# MCU089A_AltRouting_Misc.net
KiCad netlist of a schematic drawn in Altium Designer
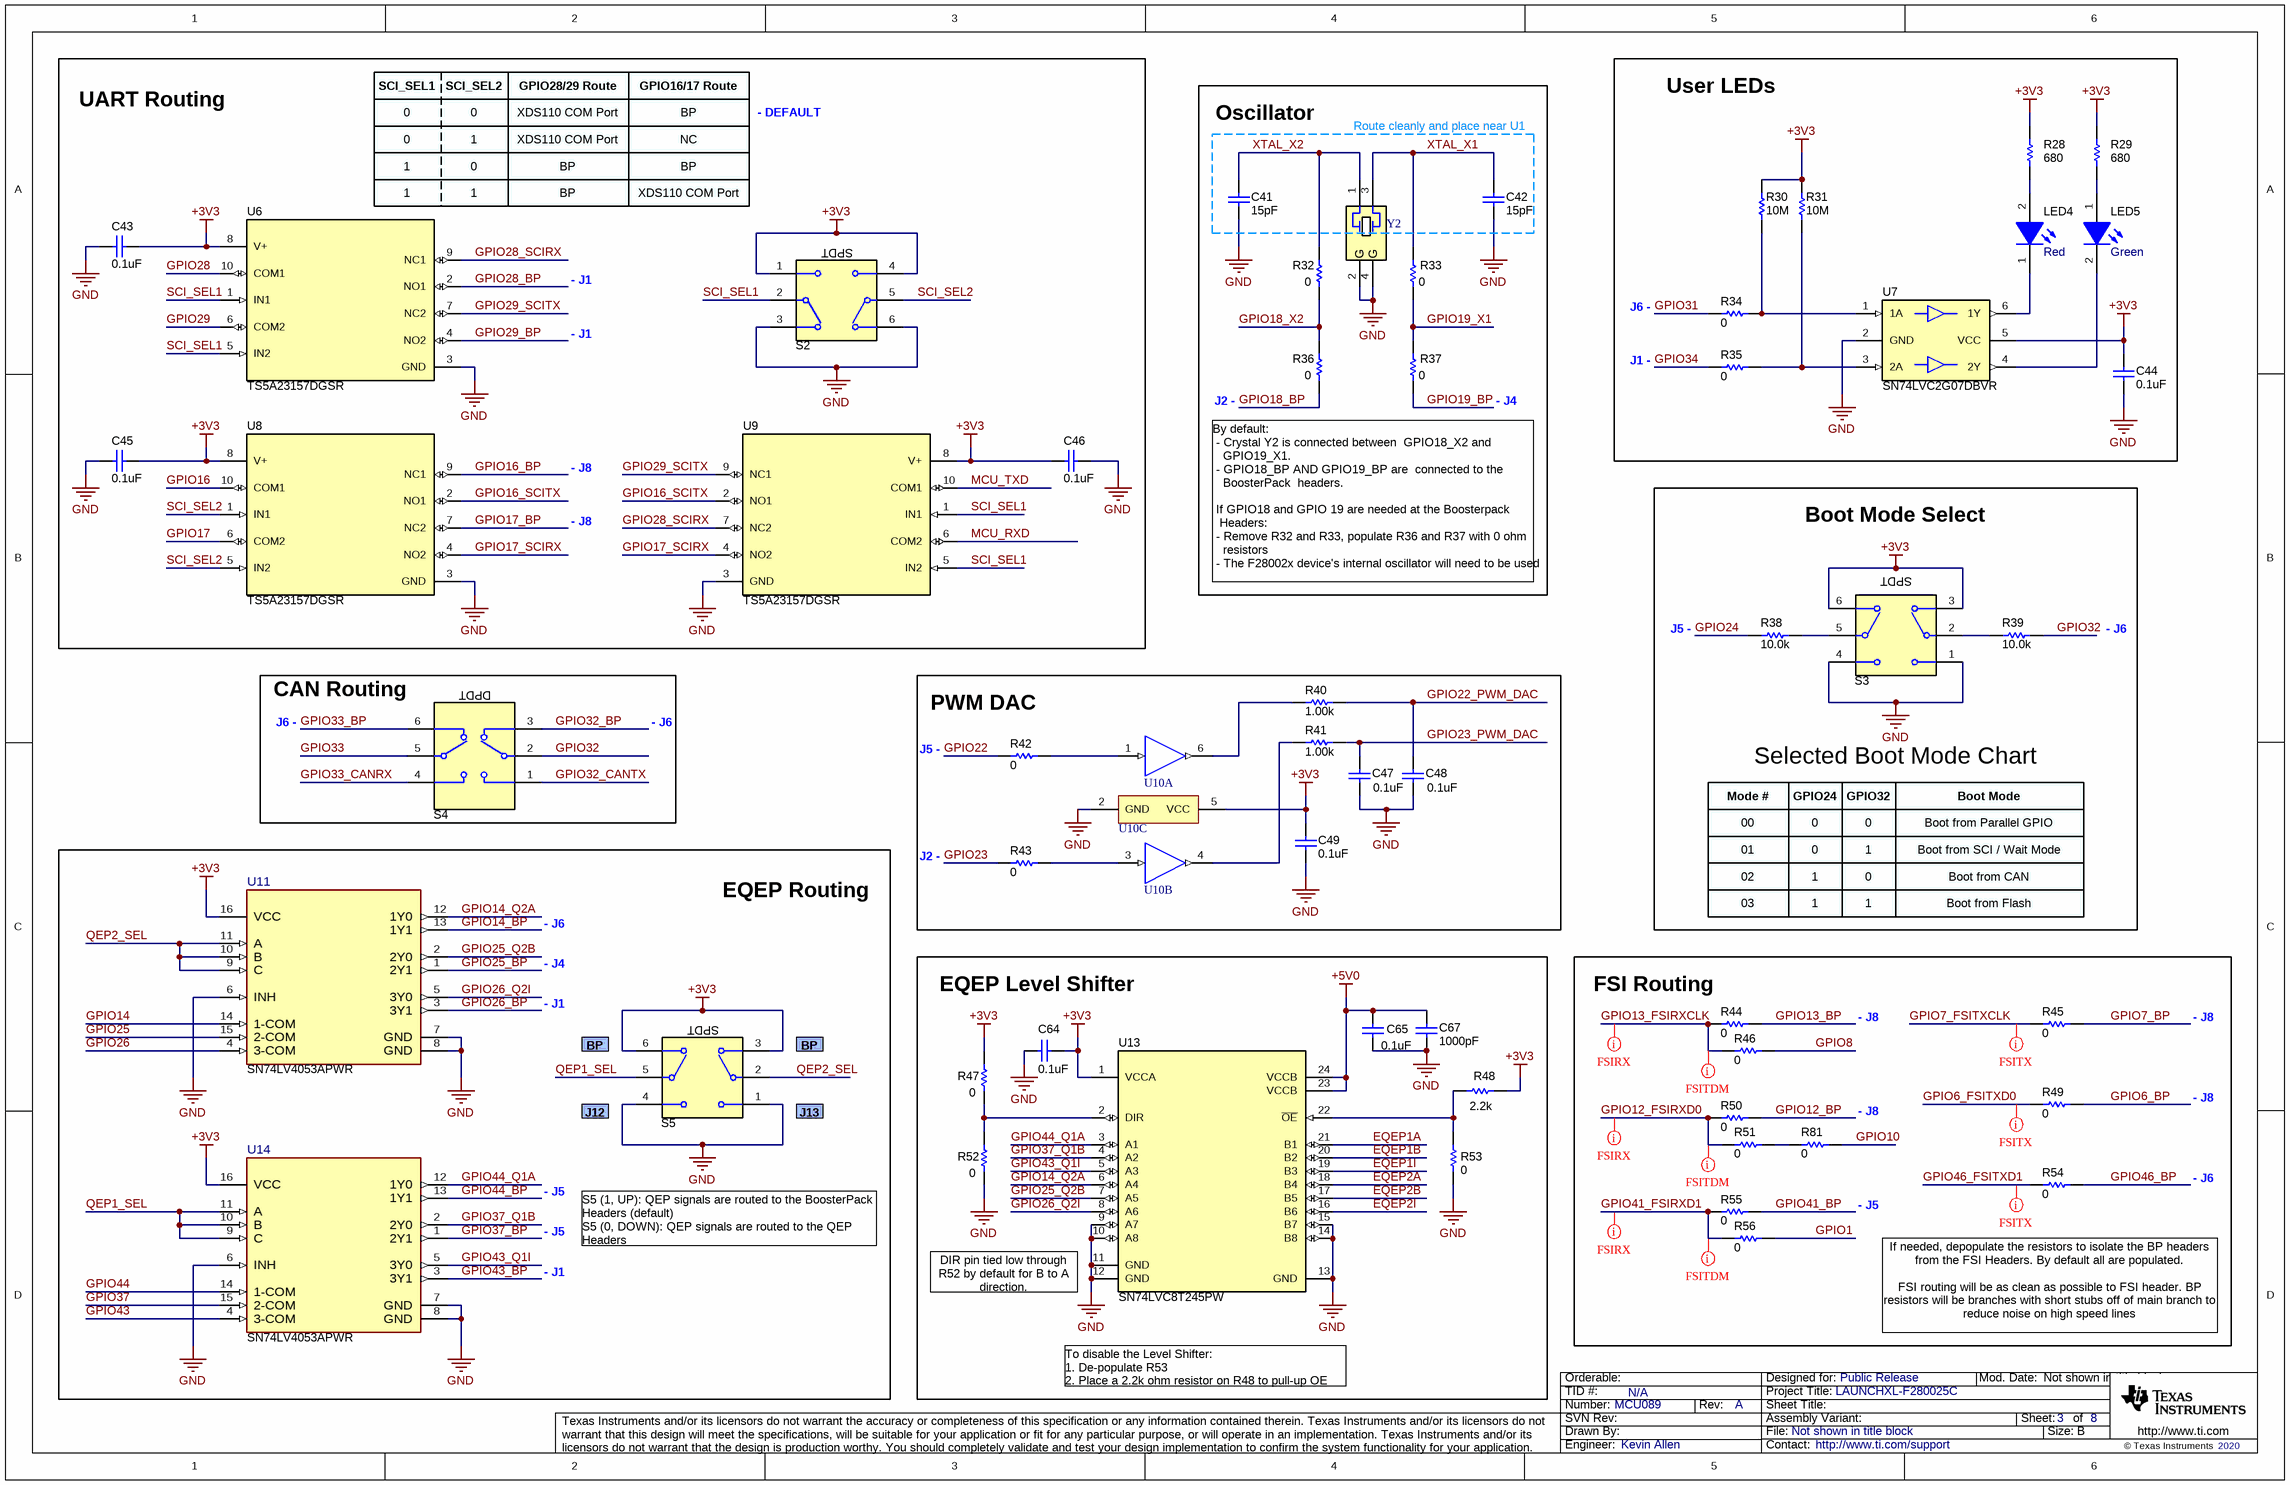
[diagram p0: MCU089A_AltRouting_Misc.SchDoc]

(export (version "E")
  (design (tool "Eeschema 10.0.6"))
  (components
    (comp (ref "C41")
      (value "885012005056")
      (footprint "0402")
      (description "CAP, CERM, 15 pF, 50 V, +/- 5%, C0G/NP0, 0402")
      (fields
        (field (name "VALUEDISPLAYED") "15pF")
        (field (name "MANUFACTURER") "Wurth Elektronik")
        (field (name "PUBLISHER") "Texas Instruments")
      )
      (libsource (lib "Altium Vault - TI") (part "Capacitor"))
    )
    (comp (ref "C42")
      (value "885012005056")
      (footprint "0402")
      (description "CAP, CERM, 15 pF, 50 V, +/- 5%, C0G/NP0, 0402")
      (fields
        (field (name "VALUEDISPLAYED") "15pF")
        (field (name "MANUFACTURER") "Wurth Elektronik")
        (field (name "PUBLISHER") "Texas Instruments")
      )
      (libsource (lib "Altium Vault - TI") (part "Capacitor"))
    )
    (comp (ref "C43")
      (value "GRM155R71A104KA01D")
      (footprint "0402")
      (description "CAP, CERM, 0.1 uF, 10 V, +/- 10%, X7R, 0402")
      (fields
        (field (name "VALUEDISPLAYED") "0.1uF")
        (field (name "MANUFACTURER") "MuRata")
        (field (name "PUBLISHER") "Texas Instruments")
      )
      (libsource (lib "Altium Vault - TI") (part "Capacitor"))
    )
    (comp (ref "C44")
      (value "GRM155R71A104KA01D")
      (footprint "0402")
      (description "CAP, CERM, 0.1 uF, 10 V, +/- 10%, X7R, 0402")
      (fields
        (field (name "VALUEDISPLAYED") "0.1uF")
        (field (name "MANUFACTURER") "MuRata")
        (field (name "PUBLISHER") "Texas Instruments")
      )
      (libsource (lib "Altium Vault - TI") (part "Capacitor"))
    )
    (comp (ref "C45")
      (value "GRM155R71A104KA01D")
      (footprint "0402")
      (description "CAP, CERM, 0.1 uF, 10 V, +/- 10%, X7R, 0402")
      (fields
        (field (name "VALUEDISPLAYED") "0.1uF")
        (field (name "MANUFACTURER") "MuRata")
        (field (name "PUBLISHER") "Texas Instruments")
      )
      (libsource (lib "Altium Vault - TI") (part "Capacitor"))
    )
    (comp (ref "C46")
      (value "GRM155R71A104KA01D")
      (footprint "0402")
      (description "CAP, CERM, 0.1 uF, 10 V, +/- 10%, X7R, 0402")
      (fields
        (field (name "VALUEDISPLAYED") "0.1uF")
        (field (name "MANUFACTURER") "MuRata")
        (field (name "PUBLISHER") "Texas Instruments")
      )
      (libsource (lib "Altium Vault - TI") (part "Capacitor"))
    )
    (comp (ref "C47")
      (value "TMK105B7104MV-FR")
      (footprint "0402")
      (description "CAP, CERM, 0.1 uF, 25 V, +/- 20%, X7R, 0402")
      (fields
        (field (name "MANUFACTURER") "Taiyo Yuden")
        (field (name "VALUEDISPLAYED") "0.1uF")
        (field (name "PUBLISHER") "Texas Instruments")
      )
      (libsource (lib "Altium Vault - TI") (part "Capacitor"))
    )
    (comp (ref "C48")
      (value "TMK105B7104MV-FR")
      (footprint "0402")
      (description "CAP, CERM, 0.1 uF, 25 V, +/- 20%, X7R, 0402")
      (fields
        (field (name "MANUFACTURER") "Taiyo Yuden")
        (field (name "VALUEDISPLAYED") "0.1uF")
        (field (name "PUBLISHER") "Texas Instruments")
      )
      (libsource (lib "Altium Vault - TI") (part "Capacitor"))
    )
    (comp (ref "C49")
      (value "GRM155R71A104KA01D")
      (footprint "0402")
      (description "CAP, CERM, 0.1 uF, 10 V, +/- 10%, X7R, 0402")
      (fields
        (field (name "VALUEDISPLAYED") "0.1uF")
        (field (name "MANUFACTURER") "MuRata")
        (field (name "PUBLISHER") "Texas Instruments")
      )
      (libsource (lib "Altium Vault - TI") (part "Capacitor"))
    )
    (comp (ref "C64")
      (value "GRM155R71A104KA01D")
      (footprint "0402")
      (description "CAP, CERM, 0.1 uF, 10 V, +/- 10%, X7R, 0402")
      (fields
        (field (name "VALUEDISPLAYED") "0.1uF")
        (field (name "MANUFACTURER") "MuRata")
        (field (name "PUBLISHER") "Texas Instruments")
      )
      (libsource (lib "Altium Vault - TI") (part "Capacitor"))
    )
    (comp (ref "C65")
      (value "GRM155R71A104KA01D")
      (footprint "0402")
      (description "CAP, CERM, 0.1 uF, 10 V, +/- 10%, X7R, 0402")
      (fields
        (field (name "VALUEDISPLAYED") "0.1uF")
        (field (name "MANUFACTURER") "MuRata")
        (field (name "PUBLISHER") "Texas Instruments")
      )
      (libsource (lib "Altium Vault - TI") (part "Capacitor"))
    )
    (comp (ref "C67")
      (value "885012205061")
      (footprint "0402")
      (description "CAP, CERM, 1000 pF, 50 V, +/- 10%, X7R, 0402")
      (fields
        (field (name "VALUEDISPLAYED") "1000pF")
        (field (name "MANUFACTURER") "Wurth Elektronik")
        (field (name "PUBLISHER") "Texas Instruments")
      )
      (libsource (lib "Altium Vault - TI") (part "Capacitor"))
    )
    (comp (ref "LED4")
      (value "Red")
      (footprint "WL-SMCW_RED_0805")
      (description "LED, Red, SMD")
      (fields (field (name "MANUFACTURER") "Wurth Elektronik") (field (name "PARTNUMBER") "150080SS75000"))
      (libsource (lib "Altium Vault - TI") (part "LED_A2_K1"))
    )
    (comp (ref "LED5")
      (value "Green")
      (footprint "LED_LTST-C171")
      (description "LED, Green, SMD")
      (fields (field (name "MANUFACTURER") "Lite-On") (field (name "PARTNUMBER") "LTST-C171GKT"))
      (libsource (lib "Altium Vault - TI") (part "LED"))
    )
    (comp (ref "R28")
      (value "CRCW0402680RJNED")
      (footprint "0402")
      (description "RES, 680, 5%, 0.063 W, AEC-Q200 Grade 0, 0402")
      (fields (field (name "MANUFACTURER") "Vishay-Dale") (field (name "VALUEDISPLAYED") "680"))
      (libsource (lib "Altium Vault - TI") (part "CMP-0026962-3"))
    )
    (comp (ref "R29")
      (value "CRCW0402680RJNED")
      (footprint "0402")
      (description "RES, 680, 5%, 0.063 W, AEC-Q200 Grade 0, 0402")
      (fields (field (name "MANUFACTURER") "Vishay-Dale") (field (name "VALUEDISPLAYED") "680"))
      (libsource (lib "Altium Vault - TI") (part "CMP-0026962-3"))
    )
    (comp (ref "R30")
      (value "CRCW040210M0JNED")
      (footprint "0402")
      (description "RES, 10 M, 5%, 0.063 W, AEC-Q200 Grade 0, 0402")
      (fields (field (name "VALUEDISPLAYED") "10M") (field (name "MANUFACTURER") "Vishay-Dale"))
      (libsource (lib "Altium Vault - TI") (part "Resistor"))
    )
    (comp (ref "R31")
      (value "CRCW040210M0JNED")
      (footprint "0402")
      (description "RES, 10 M, 5%, 0.063 W, AEC-Q200 Grade 0, 0402")
      (fields (field (name "VALUEDISPLAYED") "10M") (field (name "MANUFACTURER") "Vishay-Dale"))
      (libsource (lib "Altium Vault - TI") (part "Resistor"))
    )
    (comp (ref "R32")
      (value "CRCW06030000Z0EA")
      (footprint "0603")
      (description "RES, 0, 5%, 0.1 W, AEC-Q200 Grade 0, 0603")
      (fields (field (name "VALUEDISPLAYED") "0") (field (name "MANUFACTURER") "Vishay-Dale"))
      (libsource (lib "Altium Vault - TI") (part "Resistor"))
    )
    (comp (ref "R33")
      (value "CRCW06030000Z0EA")
      (footprint "0603")
      (description "RES, 0, 5%, 0.1 W, AEC-Q200 Grade 0, 0603")
      (fields (field (name "VALUEDISPLAYED") "0") (field (name "MANUFACTURER") "Vishay-Dale"))
      (libsource (lib "Altium Vault - TI") (part "Resistor"))
    )
    (comp (ref "R34")
      (value "CRCW06030000Z0EA")
      (footprint "0603")
      (description "RES, 0, 5%, 0.1 W, AEC-Q200 Grade 0, 0603")
      (fields (field (name "VALUEDISPLAYED") "0") (field (name "MANUFACTURER") "Vishay-Dale"))
      (libsource (lib "Altium Vault - TI") (part "Resistor"))
    )
    (comp (ref "R35")
      (value "CRCW06030000Z0EA")
      (footprint "0603")
      (description "RES, 0, 5%, 0.1 W, AEC-Q200 Grade 0, 0603")
      (fields (field (name "VALUEDISPLAYED") "0") (field (name "MANUFACTURER") "Vishay-Dale"))
      (libsource (lib "Altium Vault - TI") (part "Resistor"))
    )
    (comp (ref "R36")
      (value "CRCW06030000Z0EA")
      (footprint "0603")
      (description "RES, 0, 5%, 0.1 W, AEC-Q200 Grade 0, 0603")
      (fields (field (name "VALUEDISPLAYED") "0") (field (name "MANUFACTURER") "Vishay-Dale"))
      (libsource (lib "Altium Vault - TI") (part "Resistor"))
    )
    (comp (ref "R37")
      (value "CRCW06030000Z0EA")
      (footprint "0603")
      (description "RES, 0, 5%, 0.1 W, AEC-Q200 Grade 0, 0603")
      (fields (field (name "VALUEDISPLAYED") "0") (field (name "MANUFACTURER") "Vishay-Dale"))
      (libsource (lib "Altium Vault - TI") (part "Resistor"))
    )
    (comp (ref "R38")
      (value "RC0603FR-0710KL")
      (footprint "0603")
      (description "RES, 10.0 k, 1%, 0.1 W, 0603")
      (fields (field (name "MANUFACTURER") "Yageo") (field (name "VALUEDISPLAYED") "10.0k"))
      (libsource (lib "Altium Vault - TI") (part "Resistor"))
    )
    (comp (ref "R39")
      (value "RC0603FR-0710KL")
      (footprint "0603")
      (description "RES, 10.0 k, 1%, 0.1 W, 0603")
      (fields (field (name "MANUFACTURER") "Yageo") (field (name "VALUEDISPLAYED") "10.0k"))
      (libsource (lib "Altium Vault - TI") (part "Resistor"))
    )
    (comp (ref "R40")
      (value "CRCW04021K00FKED")
      (footprint "0402")
      (description "RES, 1.00 k, 1%, 0.063 W, AEC-Q200 Grade 0, 0402")
      (fields (field (name "MANUFACTURER") "Vishay-Dale") (field (name "VALUEDISPLAYED") "1.00k"))
      (libsource (lib "Altium Vault - TI") (part "Resistor"))
    )
    (comp (ref "R41")
      (value "CRCW04021K00FKED")
      (footprint "0402")
      (description "RES, 1.00 k, 1%, 0.063 W, AEC-Q200 Grade 0, 0402")
      (fields (field (name "MANUFACTURER") "Vishay-Dale") (field (name "VALUEDISPLAYED") "1.00k"))
      (libsource (lib "Altium Vault - TI") (part "Resistor"))
    )
    (comp (ref "R42")
      (value "CRCW06030000Z0EA")
      (footprint "0603")
      (description "RES, 0, 5%, 0.1 W, AEC-Q200 Grade 0, 0603")
      (fields (field (name "VALUEDISPLAYED") "0") (field (name "MANUFACTURER") "Vishay-Dale"))
      (libsource (lib "Altium Vault - TI") (part "Resistor"))
    )
    (comp (ref "R43")
      (value "CRCW06030000Z0EA")
      (footprint "0603")
      (description "RES, 0, 5%, 0.1 W, AEC-Q200 Grade 0, 0603")
      (fields (field (name "VALUEDISPLAYED") "0") (field (name "MANUFACTURER") "Vishay-Dale"))
      (libsource (lib "Altium Vault - TI") (part "Resistor"))
    )
    (comp (ref "R44")
      (value "CRCW06030000Z0EA")
      (footprint "0603")
      (description "RES, 0, 5%, 0.1 W, AEC-Q200 Grade 0, 0603")
      (fields (field (name "VALUEDISPLAYED") "0") (field (name "MANUFACTURER") "Vishay-Dale"))
      (libsource (lib "Altium Vault - TI") (part "Resistor"))
    )
    (comp (ref "R45")
      (value "CRCW06030000Z0EA")
      (footprint "0603")
      (description "RES, 0, 5%, 0.1 W, AEC-Q200 Grade 0, 0603")
      (fields (field (name "VALUEDISPLAYED") "0") (field (name "MANUFACTURER") "Vishay-Dale"))
      (libsource (lib "Altium Vault - TI") (part "Resistor"))
    )
    (comp (ref "R46")
      (value "CRCW06030000Z0EA")
      (footprint "0603")
      (description "RES, 0, 5%, 0.1 W, AEC-Q200 Grade 0, 0603")
      (fields (field (name "VALUEDISPLAYED") "0") (field (name "MANUFACTURER") "Vishay-Dale"))
      (libsource (lib "Altium Vault - TI") (part "Resistor"))
    )
    (comp (ref "R47")
      (value "CRCW06030000Z0EA")
      (footprint "0603")
      (description "RES, 0, 5%, 0.1 W, AEC-Q200 Grade 0, 0603")
      (fields (field (name "VALUEDISPLAYED") "0") (field (name "MANUFACTURER") "Vishay-Dale"))
      (libsource (lib "Altium Vault - TI") (part "Resistor"))
    )
    (comp (ref "R48")
      (value "CRCW06032K20JNEA")
      (footprint "0603")
      (description "RES, 2.2 k, 5%, 0.1 W, AEC-Q200 Grade 0, 0603")
      (fields (field (name "VALUEDISPLAYED") "2.2k") (field (name "MANUFACTURER") "Vishay-Dale"))
      (libsource (lib "Altium Vault - TI") (part "Resistor"))
    )
    (comp (ref "R49")
      (value "CRCW06030000Z0EA")
      (footprint "0603")
      (description "RES, 0, 5%, 0.1 W, AEC-Q200 Grade 0, 0603")
      (fields (field (name "VALUEDISPLAYED") "0") (field (name "MANUFACTURER") "Vishay-Dale"))
      (libsource (lib "Altium Vault - TI") (part "Resistor"))
    )
    (comp (ref "R50")
      (value "CRCW06030000Z0EA")
      (footprint "0603")
      (description "RES, 0, 5%, 0.1 W, AEC-Q200 Grade 0, 0603")
      (fields (field (name "VALUEDISPLAYED") "0") (field (name "MANUFACTURER") "Vishay-Dale"))
      (libsource (lib "Altium Vault - TI") (part "Resistor"))
    )
    (comp (ref "R51")
      (value "CRCW06030000Z0EA")
      (footprint "0603")
      (description "RES, 0, 5%, 0.1 W, AEC-Q200 Grade 0, 0603")
      (fields (field (name "VALUEDISPLAYED") "0") (field (name "MANUFACTURER") "Vishay-Dale"))
      (libsource (lib "Altium Vault - TI") (part "Resistor"))
    )
    (comp (ref "R52")
      (value "CRCW06030000Z0EA")
      (footprint "0603")
      (description "RES, 0, 5%, 0.1 W, AEC-Q200 Grade 0, 0603")
      (fields (field (name "VALUEDISPLAYED") "0") (field (name "MANUFACTURER") "Vishay-Dale"))
      (libsource (lib "Altium Vault - TI") (part "Resistor"))
    )
    (comp (ref "R53")
      (value "CRCW06030000Z0EA")
      (footprint "0603")
      (description "RES, 0, 5%, 0.1 W, AEC-Q200 Grade 0, 0603")
      (fields (field (name "VALUEDISPLAYED") "0") (field (name "MANUFACTURER") "Vishay-Dale"))
      (libsource (lib "Altium Vault - TI") (part "Resistor"))
    )
    (comp (ref "R54")
      (value "CRCW06030000Z0EA")
      (footprint "0603")
      (description "RES, 0, 5%, 0.1 W, AEC-Q200 Grade 0, 0603")
      (fields (field (name "VALUEDISPLAYED") "0") (field (name "MANUFACTURER") "Vishay-Dale"))
      (libsource (lib "Altium Vault - TI") (part "Resistor"))
    )
    (comp (ref "R55")
      (value "CRCW06030000Z0EA")
      (footprint "0603")
      (description "RES, 0, 5%, 0.1 W, AEC-Q200 Grade 0, 0603")
      (fields (field (name "VALUEDISPLAYED") "0") (field (name "MANUFACTURER") "Vishay-Dale"))
      (libsource (lib "Altium Vault - TI") (part "Resistor"))
    )
    (comp (ref "R56")
      (value "CRCW06030000Z0EA")
      (footprint "0603")
      (description "RES, 0, 5%, 0.1 W, AEC-Q200 Grade 0, 0603")
      (fields (field (name "VALUEDISPLAYED") "0") (field (name "MANUFACTURER") "Vishay-Dale"))
      (libsource (lib "Altium Vault - TI") (part "Resistor"))
    )
    (comp (ref "R81")
      (value "CRCW06030000Z0EA")
      (footprint "0603")
      (description "RES, 0, 5%, 0.1 W, AEC-Q200 Grade 0, 0603")
      (fields (field (name "VALUEDISPLAYED") "0") (field (name "MANUFACTURER") "Vishay-Dale"))
      (libsource (lib "Altium Vault - TI") (part "Resistor"))
    )
    (comp (ref "S2")
      (value "CAS-D20TA")
      (footprint "SW_CAS-D20TA")
      (description "Switch, Dual SPDT,  2 Pos, 0.1A, 6VDC, SMD")
      (fields
        (field (name "MANUFACTURER") "Copal Electronics")
        (field (name "PUBLISHER") "Texas Instruments")
      )
      (libsource (lib "") (part "SW_SPDT_CAS-D20TA_1"))
    )
    (comp (ref "S3")
      (value "CAS-D20TA")
      (footprint "SW_CAS-D20TA")
      (description "Switch, Dual SPDT,  2 Pos, 0.1A, 6VDC, SMD")
      (fields
        (field (name "MANUFACTURER") "Copal Electronics")
        (field (name "PUBLISHER") "Texas Instruments")
      )
      (libsource (lib "Altium Vault - TI") (part "SW_SPDT_CAS-D20TA"))
    )
    (comp (ref "S4")
      (value "CAS-220TA")
      (footprint "SW_CAS-220TA")
      (description "SLIDE SWITCH DPDT  .1A, SMT")
      (fields
        (field (name "MANUFACTURER") "Copal Electronics")
        (field (name "PUBLISHER") "Texas Instruments")
      )
      (libsource (lib "Altium Vault - TI") (part "SW_CAS-220TA"))
    )
    (comp (ref "S5")
      (value "CAS-D20TA")
      (footprint "SW_CAS-D20TA")
      (description "Switch, Dual SPDT,  2 Pos, 0.1A, 6VDC, SMD")
      (fields
        (field (name "MANUFACTURER") "Copal Electronics")
        (field (name "PUBLISHER") "Texas Instruments")
      )
      (libsource (lib "Altium Vault - TI") (part "SW_SPDT_CAS-D20TA"))
    )
    (comp (ref "U6")
      (value "TS5A23157DGSR")
      (footprint "DGS0010A_N")
      (description "DUAL 10-Ohm SPDT ANALOG SWITCH, DGS0010A (VSSOP-10)")
      (fields
        (field (name "ALTERNATE PARTNUMBER") "TS5A23157DGST")
        (field (name "MANUFACTURER") "Texas Instruments")
        (field (name "PARTNUMBER") "TS5A23157DGSR")
        (field (name "PUBLISHER") "Texas Instruments")
      )
      (libsource (lib "Altium Vault - TI") (part "TS5A23159"))
    )
    (comp (ref "U7")
      (value "SN74LVC2G07DBVR")
      (footprint "DBV0006A_N")
      (description "Dual Buffer/Driver with Open-Drain Output, DBV0006A, LARGE T&R")
      (fields
        (field (name "GENERIC PART NUMBER") "SN74LVC2G07")
        (field (name "MANUFACTURER") "Texas Instruments")
      )
      (libsource (lib "Altium Vault - TI") (part "CMP-0051789-2"))
    )
    (comp (ref "U8")
      (value "TS5A23157DGSR")
      (footprint "DGS0010A_N")
      (description "DUAL 10-Ohm SPDT ANALOG SWITCH, DGS0010A (VSSOP-10)")
      (fields
        (field (name "ALTERNATE PARTNUMBER") "TS5A23157DGST")
        (field (name "MANUFACTURER") "Texas Instruments")
        (field (name "PARTNUMBER") "TS5A23157DGSR")
        (field (name "PUBLISHER") "Texas Instruments")
      )
      (libsource (lib "Altium Vault - TI") (part "TS5A23159"))
    )
    (comp (ref "U9")
      (value "TS5A23157DGSR")
      (footprint "DGS0010A_N")
      (description "DUAL 10-Ohm SPDT ANALOG SWITCH, DGS0010A (VSSOP-10)")
      (fields
        (field (name "ALTERNATE PARTNUMBER") "TS5A23157DGST")
        (field (name "MANUFACTURER") "Texas Instruments")
        (field (name "PARTNUMBER") "TS5A23157DGSR")
        (field (name "PUBLISHER") "Texas Instruments")
      )
      (libsource (lib "") (part "TS5A23159_1"))
    )
    (comp (ref "U10")
      (value "SN74LVC2G34DBVR")
      (footprint "DBV0006A_N")
      (description "Dual Buffer Gate, DBV0006A, LARGE T&R")
      (fields
        (field (name "MANUFACTURER") "Texas Instruments")
        (field (name "GENERIC PART NUMBER") "SN74LVC2G34")
      )
      (libsource (lib "") (part "TI-SN74XXX2GXXX-6_A_1"))
    )
    (comp (ref "U11")
      (value "SN74LV4053APWR")
      (footprint "PW0016A-MFG")
      (description "3 Circuit IC Switch 2:1 75Ohm 16-TSSOP")
      (fields
        (field (name "PARTNUMBER") "SN74LV4053APWR")
        (field (name "MOUSER PART NUMBER") "595-SN74LV4053APWR")
        (field (name "DIGIKEY PART NUMBER") "296-3833-1-ND")
      )
      (libsource (lib "Altium Vault - TI") (part "SYM-SN74LV4053APWR"))
    )
    (comp (ref "U13")
      (value "SN74LVC8T245PW")
      (footprint "PW0024A_N")
      (fields (field (name "MANUFACTURER") "Texas Instruments") (field (name "PARTNUMBER") "SN74LVC8T245PW"))
      (libsource (lib "Altium Vault - TI") (part "SN74LVC8T245"))
    )
    (comp (ref "U14")
      (value "SN74LV4053APWR")
      (footprint "PW0016A-MFG")
      (description "3 Circuit IC Switch 2:1 75Ohm 16-TSSOP")
      (fields
        (field (name "PARTNUMBER") "SN74LV4053APWR")
        (field (name "MOUSER PART NUMBER") "595-SN74LV4053APWR")
        (field (name "DIGIKEY PART NUMBER") "296-3833-1-ND")
      )
      (libsource (lib "Altium Vault - TI") (part "SYM-SN74LV4053APWR"))
    )
    (comp (ref "Y2")
      (value "ECS-200-18-30B-AGN-TR")
      (footprint "ECS_ECX-53B")
      (description "Crystal, 20 MHz, 25 ppm, 18 pF, SMD")
      (fields (field (name "MANUFACTURER") "ECS Inc."))
      (libsource (lib "Altium Vault - TI") (part "XTAL_4P_13_G24"))
    )
  )
  (nets
    (net (code "1") (name "+3V3") (class "Default")
      (node (ref "C43") (pin "1") (pinfunction "1_1") (pintype "passive"))
      (node (ref "C44") (pin "2") (pinfunction "2_2") (pintype "passive"))
      (node (ref "C45") (pin "1") (pinfunction "1_1") (pintype "passive"))
      (node (ref "C46") (pin "2") (pinfunction "2_2") (pintype "passive"))
      (node (ref "C49") (pin "2") (pinfunction "2_2") (pintype "passive"))
      (node (ref "C64") (pin "1") (pinfunction "1_1") (pintype "passive"))
      (node (ref "R28") (pin "2") (pinfunction "2_2") (pintype "passive"))
      (node (ref "R29") (pin "2") (pinfunction "2_2") (pintype "passive"))
      (node (ref "R30") (pin "2") (pinfunction "2_2") (pintype "passive"))
      (node (ref "R31") (pin "2") (pinfunction "2_2") (pintype "passive"))
      (node (ref "R47") (pin "2") (pinfunction "2_2") (pintype "passive"))
      (node (ref "R48") (pin "2") (pinfunction "2_2") (pintype "passive"))
      (node (ref "S2") (pin "1") (pinfunction "1_1") (pintype "passive"))
      (node (ref "S2") (pin "4") (pinfunction "4_4") (pintype "passive"))
      (node (ref "S3") (pin "3") (pinfunction "3_3") (pintype "passive"))
      (node (ref "S3") (pin "6") (pinfunction "6_6") (pintype "passive"))
      (node (ref "S5") (pin "3") (pinfunction "3_3") (pintype "passive"))
      (node (ref "S5") (pin "6") (pinfunction "6_6") (pintype "passive"))
      (node (ref "U10") (pin "5") (pinfunction "VCC_5") (pintype "power_in"))
      (node (ref "U11") (pin "16") (pinfunction "VCC_16") (pintype "power_in"))
      (node (ref "U13") (pin "1") (pinfunction "VCCA_1") (pintype "power_in"))
      (node (ref "U14") (pin "16") (pinfunction "VCC_16") (pintype "power_in"))
      (node (ref "U6") (pin "8") (pinfunction "V+_8") (pintype "power_in"))
      (node (ref "U7") (pin "5") (pinfunction "VCC_5") (pintype "power_in"))
      (node (ref "U8") (pin "8") (pinfunction "V+_8") (pintype "power_in"))
      (node (ref "U9") (pin "8") (pinfunction "V+_8") (pintype "power_in"))
    )
    (net (code "2") (name "+5V0") (class "Default")
      (node (ref "C65") (pin "2") (pinfunction "2_2") (pintype "passive"))
      (node (ref "C67") (pin "1") (pinfunction "1_1") (pintype "passive"))
      (node (ref "U13") (pin "23") (pinfunction "VCCB_23") (pintype "power_in"))
      (node (ref "U13") (pin "24") (pinfunction "VCCB_24") (pintype "power_in"))
    )
    (net (code "3") (name "/EQEP1A") (class "Default")
      (node (ref "U13") (pin "21") (pinfunction "B1_21") (pintype "bidirectional"))
    )
    (net (code "4") (name "/EQEP1B") (class "Default")
      (node (ref "U13") (pin "20") (pinfunction "B2_20") (pintype "bidirectional"))
    )
    (net (code "5") (name "/EQEP1I") (class "Default")
      (node (ref "U13") (pin "19") (pinfunction "B3_19") (pintype "bidirectional"))
    )
    (net (code "6") (name "/EQEP2A") (class "Default")
      (node (ref "U13") (pin "18") (pinfunction "B4_18") (pintype "bidirectional"))
    )
    (net (code "7") (name "/EQEP2B") (class "Default")
      (node (ref "U13") (pin "17") (pinfunction "B5_17") (pintype "bidirectional"))
    )
    (net (code "8") (name "/EQEP2I") (class "Default")
      (node (ref "U13") (pin "16") (pinfunction "B6_16") (pintype "bidirectional"))
    )
    (net (code "9") (name "/GPIO1") (class "Default")
      (node (ref "R56") (pin "2") (pinfunction "2_2") (pintype "passive"))
    )
    (net (code "10") (name "/GPIO6_BP") (class "Default")
      (node (ref "R49") (pin "2") (pinfunction "2_2") (pintype "passive"))
    )
    (net (code "11") (name "/GPIO6_FSITXD0") (class "Default")
      (node (ref "R49") (pin "1") (pinfunction "1_1") (pintype "passive"))
    )
    (net (code "12") (name "/GPIO7_BP") (class "Default")
      (node (ref "R45") (pin "2") (pinfunction "2_2") (pintype "passive"))
    )
    (net (code "13") (name "/GPIO7_FSITXCLK") (class "Default")
      (node (ref "R45") (pin "1") (pinfunction "1_1") (pintype "passive"))
    )
    (net (code "14") (name "/GPIO8") (class "Default")
      (node (ref "R46") (pin "2") (pinfunction "2_2") (pintype "passive"))
    )
    (net (code "15") (name "/GPIO10") (class "Default")
      (node (ref "R81") (pin "2") (pinfunction "2_2") (pintype "passive"))
    )
    (net (code "16") (name "/GPIO12_BP") (class "Default")
      (node (ref "R50") (pin "2") (pinfunction "2_2") (pintype "passive"))
    )
    (net (code "17") (name "/GPIO12_FSIRXD0") (class "Default")
      (node (ref "R50") (pin "1") (pinfunction "1_1") (pintype "passive"))
      (node (ref "R51") (pin "1") (pinfunction "1_1") (pintype "passive"))
    )
    (net (code "18") (name "/GPIO13_BP") (class "Default")
      (node (ref "R44") (pin "2") (pinfunction "2_2") (pintype "passive"))
    )
    (net (code "19") (name "/GPIO13_FSIRXCLK") (class "Default")
      (node (ref "R44") (pin "1") (pinfunction "1_1") (pintype "passive"))
      (node (ref "R46") (pin "1") (pinfunction "1_1") (pintype "passive"))
    )
    (net (code "20") (name "/GPIO14") (class "Default")
      (node (ref "U11") (pin "14") (pinfunction "1-COM_14") (pintype "input"))
    )
    (net (code "21") (name "/GPIO14_BP") (class "Default")
      (node (ref "U11") (pin "13") (pinfunction "1Y1_13") (pintype "output"))
    )
    (net (code "22") (name "/GPIO14_Q2A") (class "Default")
      (node (ref "U11") (pin "12") (pinfunction "1Y0_12") (pintype "output"))
      (node (ref "U13") (pin "6") (pinfunction "A4_6") (pintype "bidirectional"))
    )
    (net (code "23") (name "/GPIO16") (class "Default")
      (node (ref "U8") (pin "10") (pinfunction "COM1_10") (pintype "bidirectional"))
    )
    (net (code "24") (name "/GPIO16_BP") (class "Default")
      (node (ref "U8") (pin "9") (pinfunction "NC1_9") (pintype "bidirectional"))
    )
    (net (code "25") (name "/GPIO16_SCITX") (class "Default")
      (node (ref "U8") (pin "2") (pinfunction "NO1_2") (pintype "bidirectional"))
      (node (ref "U9") (pin "2") (pinfunction "NO1_2") (pintype "bidirectional"))
    )
    (net (code "26") (name "/GPIO17") (class "Default")
      (node (ref "U8") (pin "6") (pinfunction "COM2_6") (pintype "bidirectional"))
    )
    (net (code "27") (name "/GPIO17_BP") (class "Default")
      (node (ref "U8") (pin "7") (pinfunction "NC2_7") (pintype "bidirectional"))
    )
    (net (code "28") (name "/GPIO17_SCIRX") (class "Default")
      (node (ref "U8") (pin "4") (pinfunction "NO2_4") (pintype "bidirectional"))
      (node (ref "U9") (pin "4") (pinfunction "NO2_4") (pintype "bidirectional"))
    )
    (net (code "29") (name "/GPIO18_BP") (class "Default")
      (node (ref "R36") (pin "1") (pinfunction "1_1") (pintype "passive"))
    )
    (net (code "30") (name "/GPIO18_X2") (class "Default")
      (node (ref "R32") (pin "1") (pinfunction "1_1") (pintype "passive"))
      (node (ref "R36") (pin "2") (pinfunction "2_2") (pintype "passive"))
    )
    (net (code "31") (name "/GPIO19_BP") (class "Default")
      (node (ref "R37") (pin "1") (pinfunction "1_1") (pintype "passive"))
    )
    (net (code "32") (name "/GPIO19_X1") (class "Default")
      (node (ref "R33") (pin "1") (pinfunction "1_1") (pintype "passive"))
      (node (ref "R37") (pin "2") (pinfunction "2_2") (pintype "passive"))
    )
    (net (code "33") (name "/GPIO22") (class "Default")
      (node (ref "R42") (pin "1") (pinfunction "1_1") (pintype "passive"))
    )
    (net (code "34") (name "/GPIO22_PWM_DAC") (class "Default")
      (node (ref "C48") (pin "1") (pinfunction "1_1") (pintype "passive"))
      (node (ref "R40") (pin "2") (pinfunction "2_2") (pintype "passive"))
    )
    (net (code "35") (name "/GPIO23") (class "Default")
      (node (ref "R43") (pin "1") (pinfunction "1_1") (pintype "passive"))
    )
    (net (code "36") (name "/GPIO23_PWM_DAC") (class "Default")
      (node (ref "C47") (pin "1") (pinfunction "1_1") (pintype "passive"))
      (node (ref "R41") (pin "2") (pinfunction "2_2") (pintype "passive"))
    )
    (net (code "37") (name "/GPIO24") (class "Default")
      (node (ref "R38") (pin "1") (pinfunction "1_1") (pintype "passive"))
    )
    (net (code "38") (name "/GPIO25") (class "Default")
      (node (ref "U11") (pin "15") (pinfunction "2-COM_15") (pintype "input"))
    )
    (net (code "39") (name "/GPIO25_BP") (class "Default")
      (node (ref "U11") (pin "1") (pinfunction "2Y1_1") (pintype "output"))
    )
    (net (code "40") (name "/GPIO25_Q2B") (class "Default")
      (node (ref "U11") (pin "2") (pinfunction "2Y0_2") (pintype "output"))
      (node (ref "U13") (pin "7") (pinfunction "A5_7") (pintype "bidirectional"))
    )
    (net (code "41") (name "/GPIO26") (class "Default")
      (node (ref "U11") (pin "4") (pinfunction "3-COM_4") (pintype "input"))
    )
    (net (code "42") (name "/GPIO26_BP") (class "Default")
      (node (ref "U11") (pin "3") (pinfunction "3Y1_3") (pintype "output"))
    )
    (net (code "43") (name "/GPIO26_Q2I") (class "Default")
      (node (ref "U11") (pin "5") (pinfunction "3Y0_5") (pintype "output"))
      (node (ref "U13") (pin "8") (pinfunction "A6_8") (pintype "bidirectional"))
    )
    (net (code "44") (name "/GPIO28") (class "Default")
      (node (ref "U6") (pin "10") (pinfunction "COM1_10") (pintype "bidirectional"))
    )
    (net (code "45") (name "/GPIO28_BP") (class "Default")
      (node (ref "U6") (pin "2") (pinfunction "NO1_2") (pintype "bidirectional"))
    )
    (net (code "46") (name "/GPIO28_SCIRX") (class "Default")
      (node (ref "U6") (pin "9") (pinfunction "NC1_9") (pintype "bidirectional"))
      (node (ref "U9") (pin "7") (pinfunction "NC2_7") (pintype "bidirectional"))
    )
    (net (code "47") (name "/GPIO29") (class "Default")
      (node (ref "U6") (pin "6") (pinfunction "COM2_6") (pintype "bidirectional"))
    )
    (net (code "48") (name "/GPIO29_BP") (class "Default")
      (node (ref "U6") (pin "4") (pinfunction "NO2_4") (pintype "bidirectional"))
    )
    (net (code "49") (name "/GPIO29_SCITX") (class "Default")
      (node (ref "U6") (pin "7") (pinfunction "NC2_7") (pintype "bidirectional"))
      (node (ref "U9") (pin "9") (pinfunction "NC1_9") (pintype "bidirectional"))
    )
    (net (code "50") (name "/GPIO31") (class "Default")
      (node (ref "R34") (pin "1") (pinfunction "1_1") (pintype "passive"))
    )
    (net (code "51") (name "/GPIO32") (class "Default")
      (node (ref "R39") (pin "2") (pinfunction "2_2") (pintype "passive"))
      (node (ref "S4") (pin "2") (pinfunction "2_2") (pintype "passive"))
    )
    (net (code "52") (name "/GPIO32_BP") (class "Default")
      (node (ref "S4") (pin "3") (pinfunction "3_3") (pintype "passive"))
    )
    (net (code "53") (name "/GPIO32_CANTX") (class "Default")
      (node (ref "S4") (pin "1") (pinfunction "1_1") (pintype "passive"))
    )
    (net (code "54") (name "/GPIO33") (class "Default")
      (node (ref "S4") (pin "5") (pinfunction "5_5") (pintype "passive"))
    )
    (net (code "55") (name "/GPIO33_BP") (class "Default")
      (node (ref "S4") (pin "6") (pinfunction "6_6") (pintype "passive"))
    )
    (net (code "56") (name "/GPIO33_CANRX") (class "Default")
      (node (ref "S4") (pin "4") (pinfunction "4_4") (pintype "passive"))
    )
    (net (code "57") (name "/GPIO34") (class "Default")
      (node (ref "R35") (pin "1") (pinfunction "1_1") (pintype "passive"))
    )
    (net (code "58") (name "/GPIO37") (class "Default")
      (node (ref "U14") (pin "15") (pinfunction "2-COM_15") (pintype "input"))
    )
    (net (code "59") (name "/GPIO37_BP") (class "Default")
      (node (ref "U14") (pin "1") (pinfunction "2Y1_1") (pintype "output"))
    )
    (net (code "60") (name "/GPIO37_Q1B") (class "Default")
      (node (ref "U13") (pin "4") (pinfunction "A2_4") (pintype "bidirectional"))
      (node (ref "U14") (pin "2") (pinfunction "2Y0_2") (pintype "output"))
    )
    (net (code "61") (name "/GPIO41_BP") (class "Default")
      (node (ref "R55") (pin "2") (pinfunction "2_2") (pintype "passive"))
    )
    (net (code "62") (name "/GPIO41_FSIRXD1") (class "Default")
      (node (ref "R55") (pin "1") (pinfunction "1_1") (pintype "passive"))
      (node (ref "R56") (pin "1") (pinfunction "1_1") (pintype "passive"))
    )
    (net (code "63") (name "/GPIO43") (class "Default")
      (node (ref "U14") (pin "4") (pinfunction "3-COM_4") (pintype "input"))
    )
    (net (code "64") (name "/GPIO43_BP") (class "Default")
      (node (ref "U14") (pin "3") (pinfunction "3Y1_3") (pintype "output"))
    )
    (net (code "65") (name "/GPIO43_Q1I") (class "Default")
      (node (ref "U13") (pin "5") (pinfunction "A3_5") (pintype "bidirectional"))
      (node (ref "U14") (pin "5") (pinfunction "3Y0_5") (pintype "output"))
    )
    (net (code "66") (name "/GPIO44") (class "Default")
      (node (ref "U14") (pin "14") (pinfunction "1-COM_14") (pintype "input"))
    )
    (net (code "67") (name "/GPIO44_BP") (class "Default")
      (node (ref "U14") (pin "13") (pinfunction "1Y1_13") (pintype "output"))
    )
    (net (code "68") (name "/GPIO44_Q1A") (class "Default")
      (node (ref "U13") (pin "3") (pinfunction "A1_3") (pintype "bidirectional"))
      (node (ref "U14") (pin "12") (pinfunction "1Y0_12") (pintype "output"))
    )
    (net (code "69") (name "/GPIO46_BP") (class "Default")
      (node (ref "R54") (pin "2") (pinfunction "2_2") (pintype "passive"))
    )
    (net (code "70") (name "/GPIO46_FSITXD1") (class "Default")
      (node (ref "R54") (pin "1") (pinfunction "1_1") (pintype "passive"))
    )
    (net (code "71") (name "/MCU_RXD") (class "Default")
      (node (ref "U9") (pin "6") (pinfunction "COM2_6") (pintype "bidirectional"))
    )
    (net (code "72") (name "/MCU_TXD") (class "Default")
      (node (ref "U9") (pin "10") (pinfunction "COM1_10") (pintype "bidirectional"))
    )
    (net (code "73") (name "/QEP1_SEL") (class "Default")
      (node (ref "S5") (pin "5") (pinfunction "C_5") (pintype "passive"))
      (node (ref "U14") (pin "10") (pinfunction "B_10") (pintype "input"))
      (node (ref "U14") (pin "11") (pinfunction "A_11") (pintype "input"))
      (node (ref "U14") (pin "9") (pinfunction "C_9") (pintype "input"))
    )
    (net (code "74") (name "/QEP2_SEL") (class "Default")
      (node (ref "S5") (pin "2") (pinfunction "C_2") (pintype "passive"))
      (node (ref "U11") (pin "10") (pinfunction "B_10") (pintype "input"))
      (node (ref "U11") (pin "11") (pinfunction "A_11") (pintype "input"))
      (node (ref "U11") (pin "9") (pinfunction "C_9") (pintype "input"))
    )
    (net (code "75") (name "/SCI_SEL1") (class "Default")
      (node (ref "S2") (pin "2") (pinfunction "C_2") (pintype "passive"))
      (node (ref "U6") (pin "1") (pinfunction "IN1_1") (pintype "input"))
      (node (ref "U6") (pin "5") (pinfunction "IN2_5") (pintype "input"))
      (node (ref "U9") (pin "1") (pinfunction "IN1_1") (pintype "input"))
      (node (ref "U9") (pin "5") (pinfunction "IN2_5") (pintype "input"))
    )
    (net (code "76") (name "/SCI_SEL2") (class "Default")
      (node (ref "S2") (pin "5") (pinfunction "C_5") (pintype "passive"))
      (node (ref "U8") (pin "1") (pinfunction "IN1_1") (pintype "input"))
      (node (ref "U8") (pin "5") (pinfunction "IN2_5") (pintype "input"))
    )
    (net (code "77") (name "/XTAL_X1") (class "Default")
      (node (ref "C42") (pin "1") (pinfunction "1_1") (pintype "passive"))
      (node (ref "R33") (pin "2") (pinfunction "2_2") (pintype "passive"))
      (node (ref "Y2") (pin "3") (pinfunction "3_3") (pintype "passive"))
    )
    (net (code "78") (name "/XTAL_X2") (class "Default")
      (node (ref "C41") (pin "1") (pinfunction "1_1") (pintype "passive"))
      (node (ref "R32") (pin "2") (pinfunction "2_2") (pintype "passive"))
      (node (ref "Y2") (pin "1") (pinfunction "1_1") (pintype "passive"))
    )
    (net (code "79") (name "GND") (class "Default")
      (node (ref "C41") (pin "2") (pinfunction "2_2") (pintype "passive"))
      (node (ref "C42") (pin "2") (pinfunction "2_2") (pintype "passive"))
      (node (ref "C43") (pin "2") (pinfunction "2_2") (pintype "passive"))
      (node (ref "C44") (pin "1") (pinfunction "1_1") (pintype "passive"))
      (node (ref "C45") (pin "2") (pinfunction "2_2") (pintype "passive"))
      (node (ref "C46") (pin "1") (pinfunction "1_1") (pintype "passive"))
      (node (ref "C47") (pin "2") (pinfunction "2_2") (pintype "passive"))
      (node (ref "C48") (pin "2") (pinfunction "2_2") (pintype "passive"))
      (node (ref "C49") (pin "1") (pinfunction "1_1") (pintype "passive"))
      (node (ref "C64") (pin "2") (pinfunction "2_2") (pintype "passive"))
      (node (ref "C65") (pin "1") (pinfunction "1_1") (pintype "passive"))
      (node (ref "C67") (pin "2") (pinfunction "2_2") (pintype "passive"))
      (node (ref "R52") (pin "1") (pinfunction "1_1") (pintype "passive"))
      (node (ref "R53") (pin "2") (pinfunction "2_2") (pintype "passive"))
      (node (ref "S2") (pin "3") (pinfunction "3_3") (pintype "passive"))
      (node (ref "S2") (pin "6") (pinfunction "6_6") (pintype "passive"))
      (node (ref "S3") (pin "1") (pinfunction "1_1") (pintype "passive"))
      (node (ref "S3") (pin "4") (pinfunction "4_4") (pintype "passive"))
      (node (ref "S5") (pin "1") (pinfunction "1_1") (pintype "passive"))
      (node (ref "S5") (pin "4") (pinfunction "4_4") (pintype "passive"))
      (node (ref "U10") (pin "2") (pinfunction "GND_2") (pintype "power_in"))
      (node (ref "U11") (pin "6") (pinfunction "INH_6") (pintype "input"))
      (node (ref "U11") (pin "7") (pinfunction "GND_7") (pintype "power_in"))
      (node (ref "U11") (pin "8") (pinfunction "GND_8") (pintype "power_in"))
      (node (ref "U13") (pin "10") (pinfunction "A8_10") (pintype "bidirectional"))
      (node (ref "U13") (pin "11") (pinfunction "GND_11") (pintype "power_in"))
      (node (ref "U13") (pin "12") (pinfunction "GND_12") (pintype "power_in"))
      (node (ref "U13") (pin "13") (pinfunction "GND_13") (pintype "power_in"))
      (node (ref "U13") (pin "14") (pinfunction "B8_14") (pintype "bidirectional"))
      (node (ref "U13") (pin "15") (pinfunction "B7_15") (pintype "bidirectional"))
      (node (ref "U13") (pin "9") (pinfunction "A7_9") (pintype "bidirectional"))
      (node (ref "U14") (pin "6") (pinfunction "INH_6") (pintype "input"))
      (node (ref "U14") (pin "7") (pinfunction "GND_7") (pintype "power_in"))
      (node (ref "U14") (pin "8") (pinfunction "GND_8") (pintype "power_in"))
      (node (ref "U6") (pin "3") (pinfunction "GND_3") (pintype "power_in"))
      (node (ref "U7") (pin "2") (pinfunction "GND_2") (pintype "power_in"))
      (node (ref "U8") (pin "3") (pinfunction "GND_3") (pintype "power_in"))
      (node (ref "U9") (pin "3") (pinfunction "GND_3") (pintype "power_in"))
      (node (ref "Y2") (pin "2") (pinfunction "GND_2") (pintype "power_in"))
      (node (ref "Y2") (pin "4") (pinfunction "GND_4") (pintype "power_in"))
    )
    (net (code "80") (name "Net-(LED4-A)") (class "Default")
      (node (ref "LED4") (pin "2") (pinfunction "A_2") (pintype "passive"))
      (node (ref "R28") (pin "1") (pinfunction "1_1") (pintype "passive"))
    )
    (net (code "81") (name "Net-(LED4-K)") (class "Default")
      (node (ref "LED4") (pin "1") (pinfunction "K_1") (pintype "passive"))
      (node (ref "U7") (pin "6") (pinfunction "1Y_6") (pintype "output"))
    )
    (net (code "82") (name "Net-(LED5-A)") (class "Default")
      (node (ref "LED5") (pin "1") (pinfunction "A_1") (pintype "passive"))
      (node (ref "R29") (pin "1") (pinfunction "1_1") (pintype "passive"))
    )
    (net (code "83") (name "Net-(LED5-K)") (class "Default")
      (node (ref "LED5") (pin "2") (pinfunction "K_2") (pintype "passive"))
      (node (ref "U7") (pin "4") (pinfunction "2Y_4") (pintype "output"))
    )
    (net (code "84") (name "Net-(R38-Pad2)") (class "Default")
      (node (ref "R38") (pin "2") (pinfunction "2_2") (pintype "passive"))
      (node (ref "S3") (pin "5") (pinfunction "C_5") (pintype "passive"))
    )
    (net (code "85") (name "Net-(R39-Pad1)") (class "Default")
      (node (ref "R39") (pin "1") (pinfunction "1_1") (pintype "passive"))
      (node (ref "S3") (pin "2") (pinfunction "C_2") (pintype "passive"))
    )
    (net (code "86") (name "Net-(R51-Pad2)") (class "Default")
      (node (ref "R51") (pin "2") (pinfunction "2_2") (pintype "passive"))
      (node (ref "R81") (pin "1") (pinfunction "1_1") (pintype "passive"))
    )
    (net (code "87") (name "Net-(U7-1A)") (class "Default")
      (node (ref "R30") (pin "1") (pinfunction "1_1") (pintype "passive"))
      (node (ref "R34") (pin "2") (pinfunction "2_2") (pintype "passive"))
      (node (ref "U7") (pin "1") (pinfunction "1A_1") (pintype "input"))
    )
    (net (code "88") (name "Net-(U7-2A)") (class "Default")
      (node (ref "R31") (pin "1") (pinfunction "1_1") (pintype "passive"))
      (node (ref "R35") (pin "2") (pinfunction "2_2") (pintype "passive"))
      (node (ref "U7") (pin "3") (pinfunction "2A_3") (pintype "input"))
    )
    (net (code "89") (name "Net-(U10A-1A)") (class "Default")
      (node (ref "R42") (pin "2") (pinfunction "2_2") (pintype "passive"))
      (node (ref "U10") (pin "1") (pinfunction "1A_1") (pintype "input"))
    )
    (net (code "90") (name "Net-(U10A-1Y)") (class "Default")
      (node (ref "R40") (pin "1") (pinfunction "1_1") (pintype "passive"))
      (node (ref "U10") (pin "6") (pinfunction "1Y_6") (pintype "output"))
    )
    (net (code "91") (name "Net-(U10B-2A)") (class "Default")
      (node (ref "R43") (pin "2") (pinfunction "2_2") (pintype "passive"))
      (node (ref "U10") (pin "3") (pinfunction "2A_3") (pintype "input"))
    )
    (net (code "92") (name "Net-(U10B-2Y)") (class "Default")
      (node (ref "R41") (pin "1") (pinfunction "1_1") (pintype "passive"))
      (node (ref "U10") (pin "4") (pinfunction "2Y_4") (pintype "output"))
    )
    (net (code "93") (name "Net-(U13-DIR)") (class "Default")
      (node (ref "R47") (pin "1") (pinfunction "1_1") (pintype "passive"))
      (node (ref "R52") (pin "2") (pinfunction "2_2") (pintype "passive"))
      (node (ref "U13") (pin "2") (pinfunction "DIR_2") (pintype "bidirectional"))
    )
    (net (code "94") (name "Net-(U13-OE)") (class "Default")
      (node (ref "R48") (pin "1") (pinfunction "1_1") (pintype "passive"))
      (node (ref "R53") (pin "1") (pinfunction "1_1") (pintype "passive"))
      (node (ref "U13") (pin "22") (pinfunction "OE_22") (pintype "input"))
    )
  )
)
